# -_-.net
KiCad netlist of a schematic drawn in Altium Designer
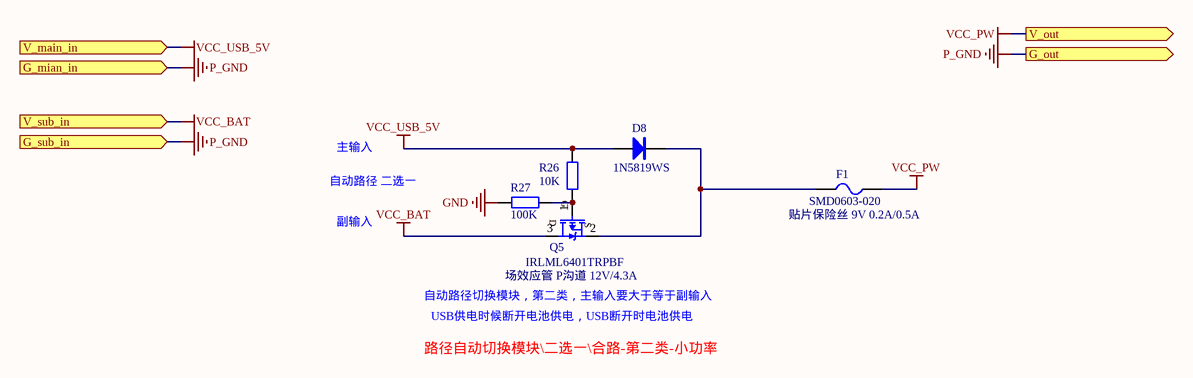
[diagram p0: 路径自动切换电路-第二类-小功率.SchDoc]

(export (version "E")
  (design (tool "Eeschema 10.0.6"))
  (components
    (comp (ref "D8")
      (value "1N5819WS")
      (footprint "SOD-323")
      (description "肖特基二极管")
      (fields (field (name "版权归属") "源创客"))
      (libsource (lib "8.1   - 二极管-整流桥") (part "1N5819"))
    )
    (comp (ref "F1")
      (value "SMD0603-020")
      (footprint "FU 0603")
      (description "贴片保险丝 9V 0.2A/0.5A")
      (fields (field (name "BOM名称") "贴片保险丝 9V 0.2A/0.5A") (field (name "版权归属") "源创客"))
      (libsource (lib "10.1 - 保险丝-晶振") (part "FU"))
    )
    (comp (ref "Q5")
      (value "IRLML6401TRPBF")
      (footprint "SOT23-3N")
      (description "场效应管 P沟道 12V/4.3A")
      (fields (field (name "BOM名称") "场效应管 P沟道 12V/4.3A") (field (name "版权归属") "源创客"))
      (libsource (lib "Foundation_temp") (part "P-MOS"))
    )
    (comp (ref "R26")
      (value "10K")
      (footprint "R 0402_L")
      (description "贴片电阻 E-96 1%")
      (libsource (lib "Foundation_temp") (part "R"))
    )
    (comp (ref "R27")
      (value "100K")
      (footprint "R 0402_L")
      (description "贴片电阻 E-96 1%")
      (libsource (lib "Foundation_temp") (part "R"))
    )
  )
  (nets
    (net (code "1") (name "GND") (class "Default")
      (node (ref "R27") (pin "1") (pinfunction "1_1") (pintype "passive"))
    )
    (net (code "2") (name "Net-(D8-K)") (class "Default")
      (node (ref "D8") (pin "2") (pinfunction "K_2") (pintype "passive"))
      (node (ref "F1") (pin "2") (pinfunction "2_2") (pintype "passive"))
      (node (ref "Q5") (pin "2") (pinfunction "S_2") (pintype "passive"))
    )
    (net (code "3") (name "Net-(Q5-G)") (class "Default")
      (node (ref "Q5") (pin "1") (pinfunction "G_1") (pintype "passive"))
      (node (ref "R26") (pin "1") (pinfunction "1_1") (pintype "passive"))
      (node (ref "R27") (pin "2") (pinfunction "2_2") (pintype "passive"))
    )
    (net (code "5") (name "VCC_BAT") (class "Default")
      (node (ref "Q5") (pin "3") (pinfunction "D_3") (pintype "passive"))
    )
    (net (code "6") (name "VCC_PW") (class "Default")
      (node (ref "F1") (pin "1") (pinfunction "1_1") (pintype "passive"))
    )
    (net (code "7") (name "VCC_USB_5V") (class "Default")
      (node (ref "D8") (pin "1") (pinfunction "A_1") (pintype "passive"))
      (node (ref "R26") (pin "2") (pinfunction "2_2") (pintype "passive"))
    )
  )
)
